# lightcontrol.net
KiCad netlist of a schematic drawn in EAGLE
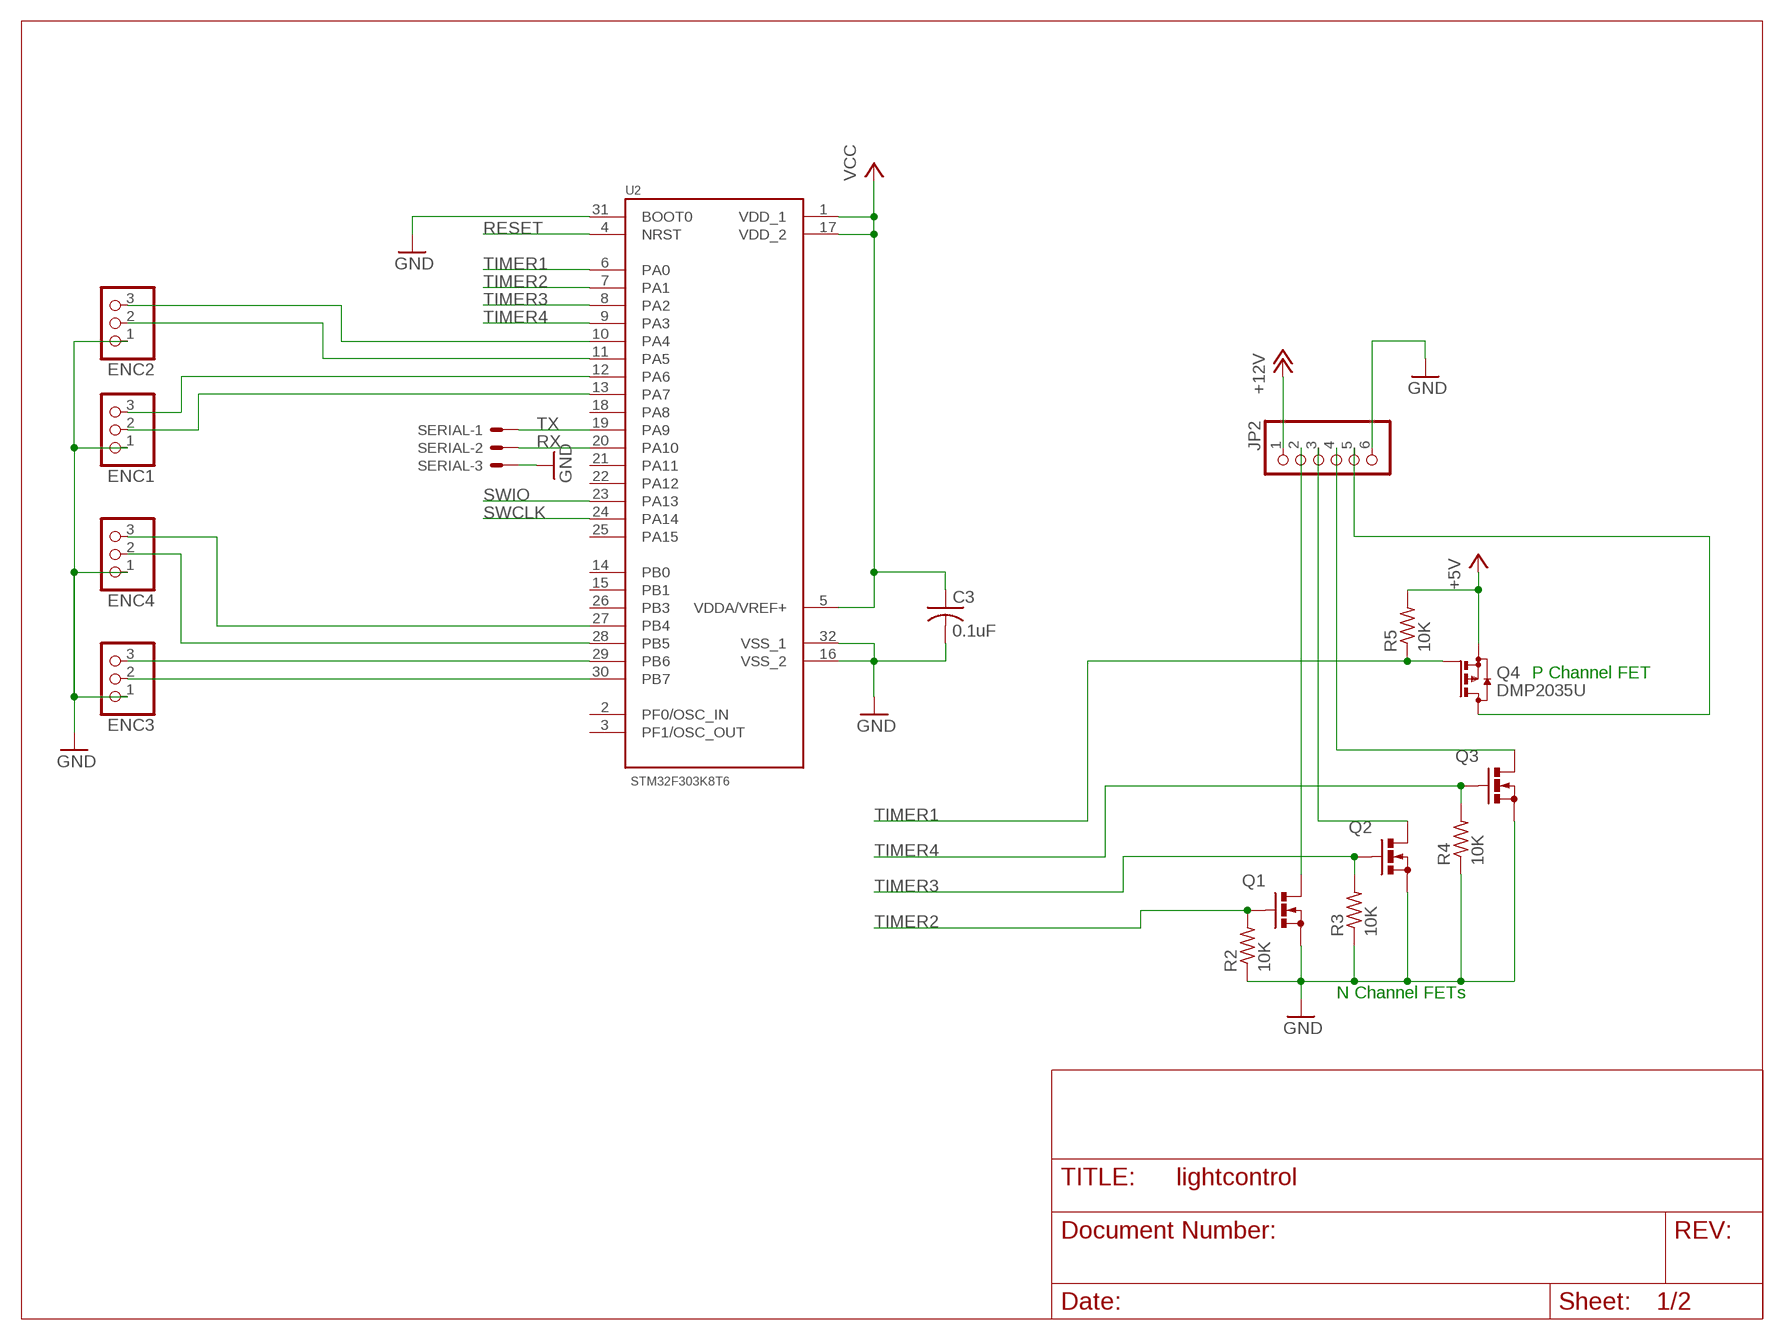
[diagram p0: schematic, sheet 1]
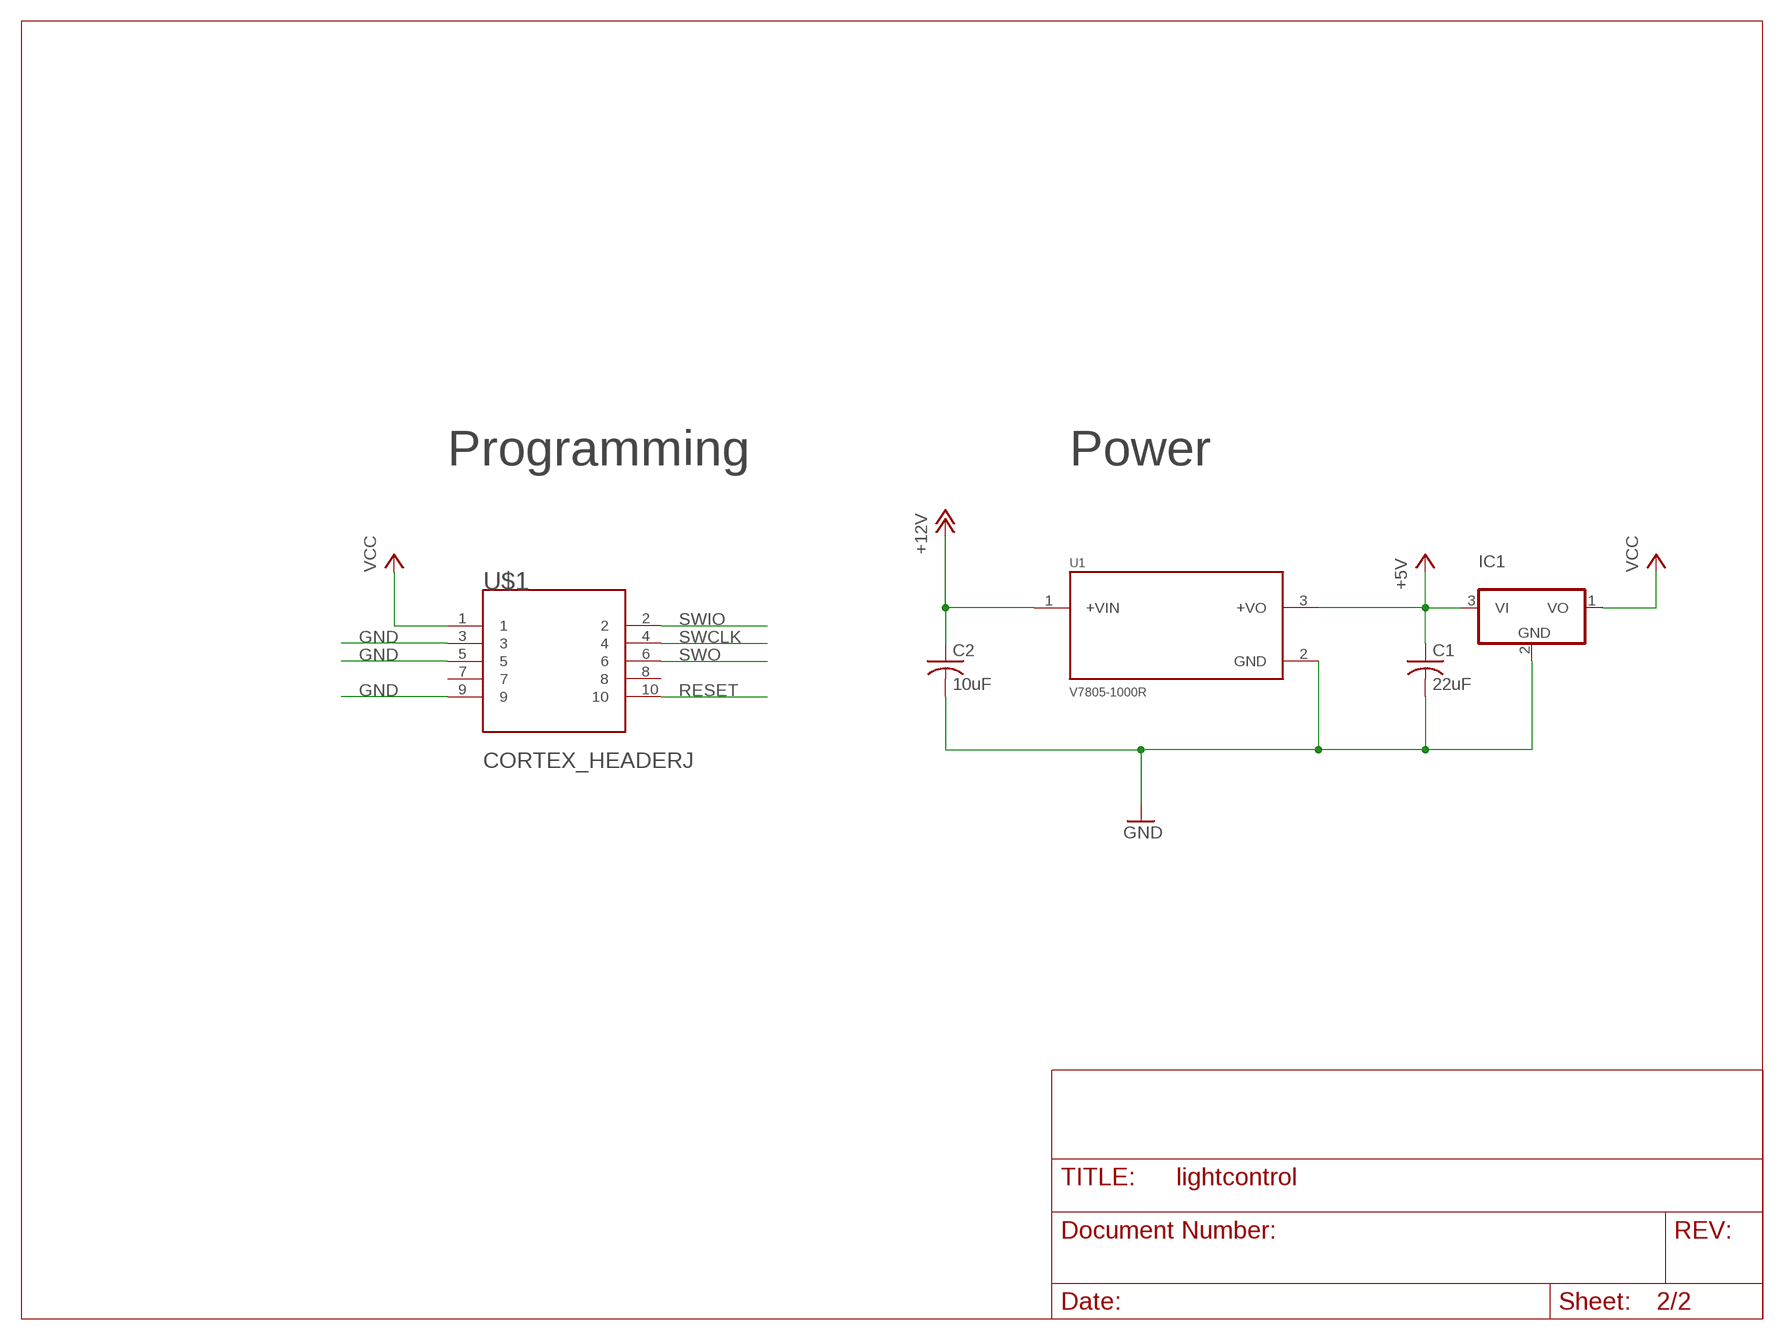
[diagram p1: schematic, sheet 2]

(export (version "E")
  (design (tool "Eeschema 10.0.6"))
  (components
    (comp (ref "C1")
      (value "22uF")
      (footprint "eagle-import:C050-035X075")
      (libsource (lib "eagle-import") (part "C-US050-035X075"))
    )
    (comp (ref "C2")
      (value "10uF")
      (footprint "eagle-import:C050-035X075")
      (libsource (lib "eagle-import") (part "C-US050-035X075"))
    )
    (comp (ref "IC1")
      (value "7803")
      (footprint "eagle-import:TO92")
      (libsource (lib "eagle-import") (part "78ZL05"))
    )
    (comp (ref "U$1")
      (value "CORTEX_HEADERJ")
      (footprint "eagle-import:CORTEX_HEADER")
      (fields (field (name "MF") "Samtec Inc.") (field (name "MP") "TFM-105-01-S-D-WT"))
      (libsource (lib "eagle-import") (part "CORTEX_HEADERJ"))
    )
    (comp (ref "U1")
      (value "V7805-1000R")
      (footprint "eagle-import:CONV_V7805-1000R")
      (fields (field (name "DIGI-KEY_PART_NUMBER") "102-2178-ND") (field (name "MF") "CUI Inc."))
      (libsource (lib "eagle-import") (part "V7805-1000R"))
    )
    (comp (ref "C3")
      (value "0.1uF")
      (footprint "eagle-import:C0603")
      (libsource (lib "eagle-import") (part "rcl_334_C-USC0603"))
    )
    (comp (ref "ENC1")
      (value "PINHD-1X3")
      (footprint "eagle-import:1X03")
      (libsource (lib "eagle-import") (part "PINHD-1X3"))
    )
    (comp (ref "ENC2")
      (value "PINHD-1X3")
      (footprint "eagle-import:1X03")
      (libsource (lib "eagle-import") (part "PINHD-1X3"))
    )
    (comp (ref "ENC3")
      (value "PINHD-1X3")
      (footprint "eagle-import:1X03")
      (libsource (lib "eagle-import") (part "PINHD-1X3"))
    )
    (comp (ref "ENC4")
      (value "PINHD-1X3")
      (footprint "eagle-import:1X03")
      (libsource (lib "eagle-import") (part "PINHD-1X3"))
    )
    (comp (ref "JP2")
      (value "PINHD-1X6/90")
      (footprint "eagle-import:1X06_90")
      (libsource (lib "eagle-import") (part "PINHD-1X6/90"))
    )
    (comp (ref "Q1")
      (value "BS170")
      (footprint "eagle-import:SOT54E")
      (libsource (lib "eagle-import") (part "BS170"))
    )
    (comp (ref "Q2")
      (value "BS170")
      (footprint "eagle-import:SOT54E")
      (libsource (lib "eagle-import") (part "BS170"))
    )
    (comp (ref "Q3")
      (value "BS170")
      (footprint "eagle-import:SOT54E")
      (libsource (lib "eagle-import") (part "BS170"))
    )
    (comp (ref "Q4")
      (value "DMP2035U")
      (footprint "eagle-import:SOT23")
      (libsource (lib "eagle-import") (part "BSS84"))
    )
    (comp (ref "R2")
      (value "10K")
      (footprint "eagle-import:0204_5")
      (libsource (lib "eagle-import") (part "R-US_0204/5"))
    )
    (comp (ref "R3")
      (value "10K")
      (footprint "eagle-import:0204_5")
      (libsource (lib "eagle-import") (part "R-US_0204/5"))
    )
    (comp (ref "R4")
      (value "10K")
      (footprint "eagle-import:0204_5")
      (libsource (lib "eagle-import") (part "R-US_0204/5"))
    )
    (comp (ref "R5")
      (value "10K")
      (footprint "eagle-import:0204_5")
      (libsource (lib "eagle-import") (part "R-US_0204/5"))
    )
    (comp (ref "SERIAL")
      (value "22-23-2031")
      (footprint "eagle-import:22-23-2031")
      (fields (field (name "MF") "MOLEX"))
      (libsource (lib "eagle-import") (part "22-23-2031"))
    )
    (comp (ref "U2")
      (value "STM32F303K8T6")
      (footprint "eagle-import:QFP80P900X900X160-32N")
      (fields (field (name "MF") "STMicroelectronics"))
      (libsource (lib "eagle-import") (part "STM32F303K8T6"))
    )
  )
  (nets
    (net (code "1") (name "+5V") (class "Default")
      (node (ref "C1") (pin "1") (pinfunction "1_1") (pintype "passive"))
      (node (ref "IC1") (pin "3") (pinfunction "VI_3") (pintype "input"))
      (node (ref "Q4") (pin "2") (pinfunction "S_2") (pintype "passive"))
      (node (ref "R5") (pin "2") (pinfunction "2_2") (pintype "passive"))
      (node (ref "U1") (pin "3") (pinfunction "+VO_3") (pintype "output"))
    )
    (net (code "2") (name "+12V") (class "Default")
      (node (ref "C2") (pin "1") (pinfunction "1_1") (pintype "passive"))
      (node (ref "JP2") (pin "1") (pinfunction "1_1") (pintype "passive"))
      (node (ref "U1") (pin "1") (pinfunction "+VIN_1") (pintype "input"))
    )
    (net (code "3") (name "GND") (class "Default")
      (node (ref "C1") (pin "2") (pinfunction "2_2") (pintype "passive"))
      (node (ref "C2") (pin "2") (pinfunction "2_2") (pintype "passive"))
      (node (ref "C3") (pin "2") (pinfunction "2_2") (pintype "passive"))
      (node (ref "ENC1") (pin "1") (pinfunction "1_1") (pintype "passive"))
      (node (ref "ENC2") (pin "1") (pinfunction "1_1") (pintype "passive"))
      (node (ref "ENC3") (pin "1") (pinfunction "1_1") (pintype "passive"))
      (node (ref "ENC4") (pin "1") (pinfunction "1_1") (pintype "passive"))
      (node (ref "IC1") (pin "2") (pinfunction "GND_2") (pintype "passive"))
      (node (ref "JP2") (pin "6") (pinfunction "6_6") (pintype "passive"))
      (node (ref "Q1") (pin "S") (pinfunction "S_S") (pintype "passive"))
      (node (ref "Q2") (pin "S") (pinfunction "S_S") (pintype "passive"))
      (node (ref "Q3") (pin "S") (pinfunction "S_S") (pintype "passive"))
      (node (ref "R2") (pin "1") (pinfunction "1_1") (pintype "passive"))
      (node (ref "R3") (pin "1") (pinfunction "1_1") (pintype "passive"))
      (node (ref "R4") (pin "1") (pinfunction "1_1") (pintype "passive"))
      (node (ref "SERIAL") (pin "3") (pinfunction "S_3") (pintype "passive"))
      (node (ref "U$1") (pin "3") (pinfunction "3_3") (pintype "passive"))
      (node (ref "U$1") (pin "5") (pinfunction "5_5") (pintype "passive"))
      (node (ref "U$1") (pin "9") (pinfunction "9_9") (pintype "passive"))
      (node (ref "U1") (pin "2") (pinfunction "GND_2") (pintype "power_in"))
      (node (ref "U2") (pin "16") (pinfunction "VSS_2_16") (pintype "power_in"))
      (node (ref "U2") (pin "31") (pinfunction "BOOT0_31") (pintype "input"))
      (node (ref "U2") (pin "32") (pinfunction "VSS_1_32") (pintype "power_in"))
    )
    (net (code "4") (name "Net-(JP2-Pad2)") (class "Default")
      (node (ref "JP2") (pin "2") (pinfunction "2_2") (pintype "passive"))
      (node (ref "Q1") (pin "D") (pinfunction "D_D") (pintype "passive"))
    )
    (net (code "5") (name "Net-(JP2-Pad3)") (class "Default")
      (node (ref "JP2") (pin "3") (pinfunction "3_3") (pintype "passive"))
      (node (ref "Q2") (pin "D") (pinfunction "D_D") (pintype "passive"))
    )
    (net (code "6") (name "Net-(JP2-Pad4)") (class "Default")
      (node (ref "JP2") (pin "4") (pinfunction "4_4") (pintype "passive"))
      (node (ref "Q3") (pin "D") (pinfunction "D_D") (pintype "passive"))
    )
    (net (code "7") (name "Net-(Q4-D)") (class "Default")
      (node (ref "JP2") (pin "5") (pinfunction "5_5") (pintype "passive"))
      (node (ref "Q4") (pin "3") (pinfunction "D_3") (pintype "passive"))
    )
    (net (code "8") (name "Net-(U2-PA4)") (class "Default")
      (node (ref "ENC2") (pin "3") (pinfunction "3_3") (pintype "passive"))
      (node (ref "U2") (pin "10") (pinfunction "PA4_10") (pintype "bidirectional"))
    )
    (net (code "9") (name "Net-(U2-PA5)") (class "Default")
      (node (ref "ENC2") (pin "2") (pinfunction "2_2") (pintype "passive"))
      (node (ref "U2") (pin "11") (pinfunction "PA5_11") (pintype "bidirectional"))
    )
    (net (code "10") (name "Net-(U2-PA6)") (class "Default")
      (node (ref "ENC1") (pin "3") (pinfunction "3_3") (pintype "passive"))
      (node (ref "U2") (pin "12") (pinfunction "PA6_12") (pintype "bidirectional"))
    )
    (net (code "11") (name "Net-(U2-PA7)") (class "Default")
      (node (ref "ENC1") (pin "2") (pinfunction "2_2") (pintype "passive"))
      (node (ref "U2") (pin "13") (pinfunction "PA7_13") (pintype "bidirectional"))
    )
    (net (code "12") (name "Net-(U2-PB4)") (class "Default")
      (node (ref "ENC4") (pin "3") (pinfunction "3_3") (pintype "passive"))
      (node (ref "U2") (pin "27") (pinfunction "PB4_27") (pintype "bidirectional"))
    )
    (net (code "13") (name "Net-(U2-PB5)") (class "Default")
      (node (ref "ENC4") (pin "2") (pinfunction "2_2") (pintype "passive"))
      (node (ref "U2") (pin "28") (pinfunction "PB5_28") (pintype "bidirectional"))
    )
    (net (code "14") (name "Net-(U2-PB6)") (class "Default")
      (node (ref "ENC3") (pin "3") (pinfunction "3_3") (pintype "passive"))
      (node (ref "U2") (pin "29") (pinfunction "PB6_29") (pintype "bidirectional"))
    )
    (net (code "15") (name "Net-(U2-PB7)") (class "Default")
      (node (ref "ENC3") (pin "2") (pinfunction "2_2") (pintype "passive"))
      (node (ref "U2") (pin "30") (pinfunction "PB7_30") (pintype "bidirectional"))
    )
    (net (code "16") (name "RESET") (class "Default")
      (node (ref "U$1") (pin "10") (pinfunction "10_10") (pintype "passive"))
      (node (ref "U2") (pin "4") (pinfunction "NRST_4") (pintype "bidirectional"))
    )
    (net (code "17") (name "RX") (class "Default")
      (node (ref "SERIAL") (pin "2") (pinfunction "S_2") (pintype "passive"))
      (node (ref "U2") (pin "20") (pinfunction "PA10_20") (pintype "bidirectional"))
    )
    (net (code "18") (name "SWCLK") (class "Default")
      (node (ref "U$1") (pin "4") (pinfunction "4_4") (pintype "passive"))
      (node (ref "U2") (pin "24") (pinfunction "PA14_24") (pintype "bidirectional"))
    )
    (net (code "19") (name "SWIO") (class "Default")
      (node (ref "U$1") (pin "2") (pinfunction "2_2") (pintype "passive"))
      (node (ref "U2") (pin "23") (pinfunction "PA13_23") (pintype "bidirectional"))
    )
    (net (code "20") (name "SWO") (class "Default")
      (node (ref "U$1") (pin "6") (pinfunction "6_6") (pintype "passive"))
    )
    (net (code "21") (name "TIMER1") (class "Default")
      (node (ref "Q4") (pin "1") (pinfunction "G_1") (pintype "passive"))
      (node (ref "R5") (pin "1") (pinfunction "1_1") (pintype "passive"))
      (node (ref "U2") (pin "6") (pinfunction "PA0_6") (pintype "bidirectional"))
    )
    (net (code "22") (name "TIMER2") (class "Default")
      (node (ref "Q1") (pin "G") (pinfunction "G_G") (pintype "passive"))
      (node (ref "R2") (pin "2") (pinfunction "2_2") (pintype "passive"))
      (node (ref "U2") (pin "7") (pinfunction "PA1_7") (pintype "bidirectional"))
    )
    (net (code "23") (name "TIMER3") (class "Default")
      (node (ref "Q2") (pin "G") (pinfunction "G_G") (pintype "passive"))
      (node (ref "R3") (pin "2") (pinfunction "2_2") (pintype "passive"))
      (node (ref "U2") (pin "8") (pinfunction "PA2_8") (pintype "bidirectional"))
    )
    (net (code "24") (name "TIMER4") (class "Default")
      (node (ref "Q3") (pin "G") (pinfunction "G_G") (pintype "passive"))
      (node (ref "R4") (pin "2") (pinfunction "2_2") (pintype "passive"))
      (node (ref "U2") (pin "9") (pinfunction "PA3_9") (pintype "bidirectional"))
    )
    (net (code "25") (name "TX") (class "Default")
      (node (ref "SERIAL") (pin "1") (pinfunction "S_1") (pintype "passive"))
      (node (ref "U2") (pin "19") (pinfunction "PA9_19") (pintype "bidirectional"))
    )
    (net (code "26") (name "VCC") (class "Default")
      (node (ref "C3") (pin "1") (pinfunction "1_1") (pintype "passive"))
      (node (ref "IC1") (pin "1") (pinfunction "VO_1") (pintype "passive"))
      (node (ref "U$1") (pin "1") (pinfunction "1_1") (pintype "passive"))
      (node (ref "U2") (pin "1") (pinfunction "VDD_1_1") (pintype "power_in"))
      (node (ref "U2") (pin "17") (pinfunction "VDD_2_17") (pintype "power_in"))
      (node (ref "U2") (pin "5") (pinfunction "VDDA/VREF+_5") (pintype "power_in"))
    )
    (net (code "27") (name "unconnected-(U$1-Pad7)") (class "Default")
      (node (ref "U$1") (pin "7") (pinfunction "7_7") (pintype "passive"))
    )
    (net (code "28") (name "unconnected-(U$1-Pad8)") (class "Default")
      (node (ref "U$1") (pin "8") (pinfunction "8_8") (pintype "passive"))
    )
    (net (code "29") (name "unconnected-(U2-PA8-Pad18)") (class "Default")
      (node (ref "U2") (pin "18") (pinfunction "PA8_18") (pintype "bidirectional"))
    )
    (net (code "30") (name "unconnected-(U2-PA11-Pad21)") (class "Default")
      (node (ref "U2") (pin "21") (pinfunction "PA11_21") (pintype "bidirectional"))
    )
    (net (code "31") (name "unconnected-(U2-PA12-Pad22)") (class "Default")
      (node (ref "U2") (pin "22") (pinfunction "PA12_22") (pintype "bidirectional"))
    )
    (net (code "32") (name "unconnected-(U2-PA15-Pad25)") (class "Default")
      (node (ref "U2") (pin "25") (pinfunction "PA15_25") (pintype "bidirectional"))
    )
    (net (code "33") (name "unconnected-(U2-PB0-Pad14)") (class "Default")
      (node (ref "U2") (pin "14") (pinfunction "PB0_14") (pintype "bidirectional"))
    )
    (net (code "34") (name "unconnected-(U2-PB1-Pad15)") (class "Default")
      (node (ref "U2") (pin "15") (pinfunction "PB1_15") (pintype "bidirectional"))
    )
    (net (code "35") (name "unconnected-(U2-PB3-Pad26)") (class "Default")
      (node (ref "U2") (pin "26") (pinfunction "PB3_26") (pintype "bidirectional"))
    )
    (net (code "36") (name "unconnected-(U2-PF0{slash}OSC_IN-Pad2)") (class "Default")
      (node (ref "U2") (pin "2") (pinfunction "PF0/OSC_IN_2") (pintype "bidirectional"))
    )
    (net (code "37") (name "unconnected-(U2-PF1{slash}OSC_OUT-Pad3)") (class "Default")
      (node (ref "U2") (pin "3") (pinfunction "PF1/OSC_OUT_3") (pintype "bidirectional"))
    )
  )
)
